# STM32F103C8T6.net
KiCad netlist of a schematic drawn in Altium Designer
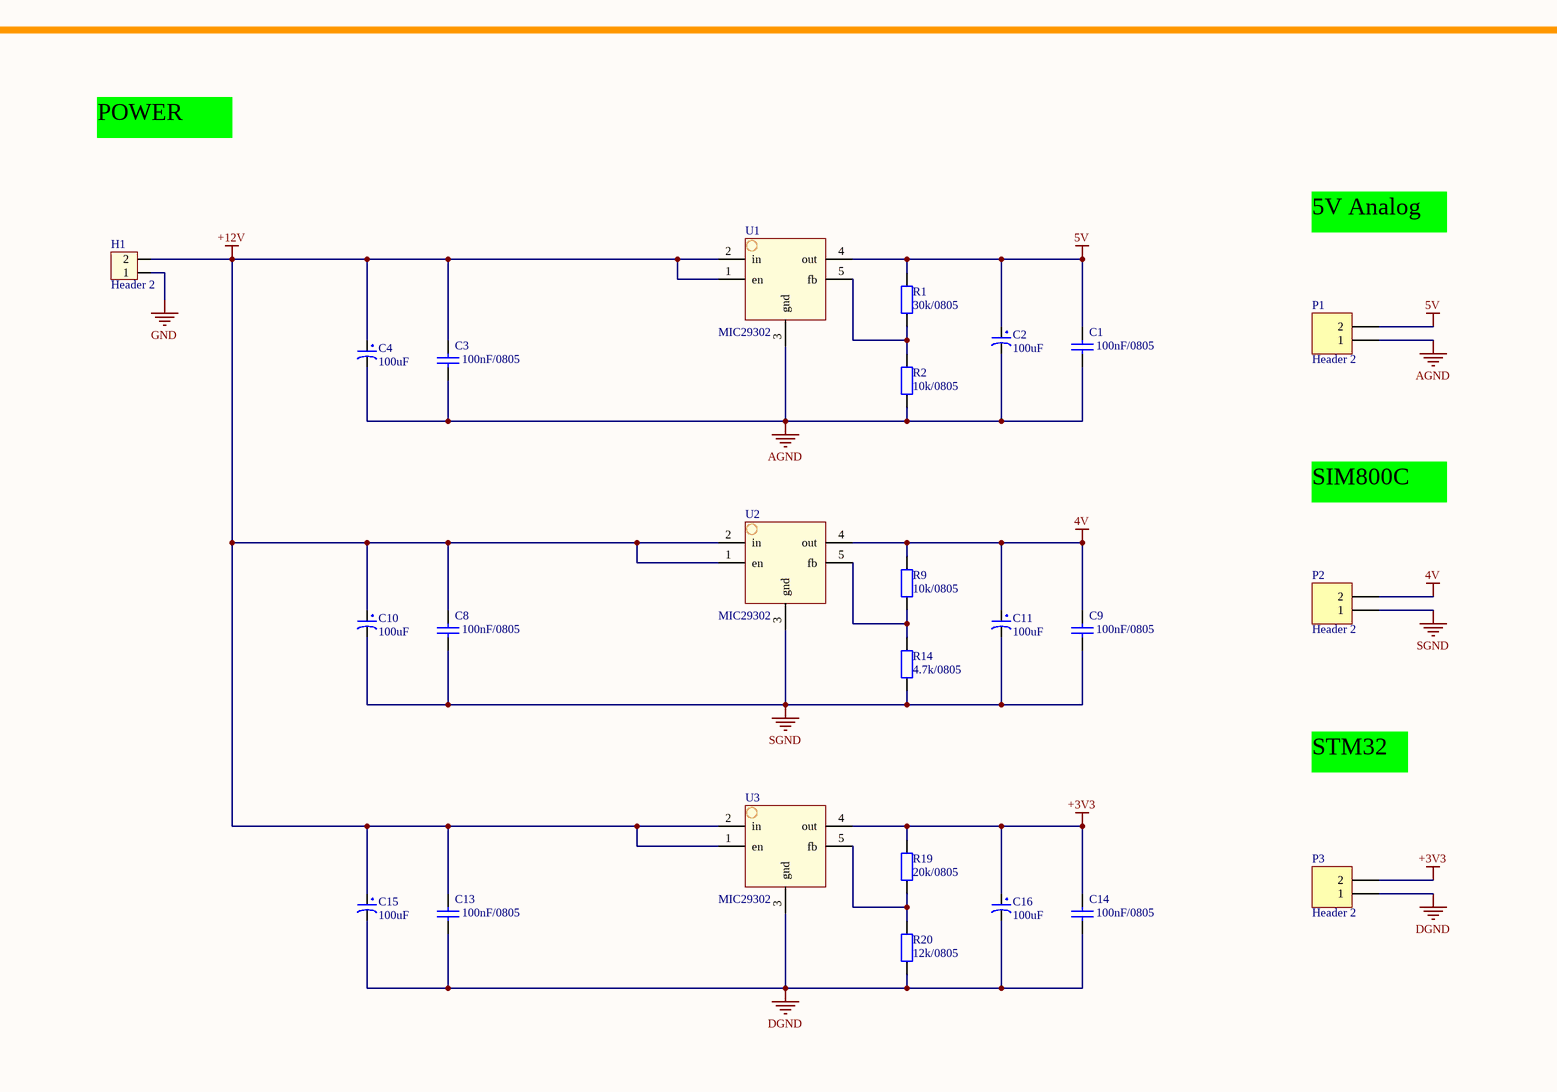
[diagram p0: STM32F103C8T6.SchDoc, top left]
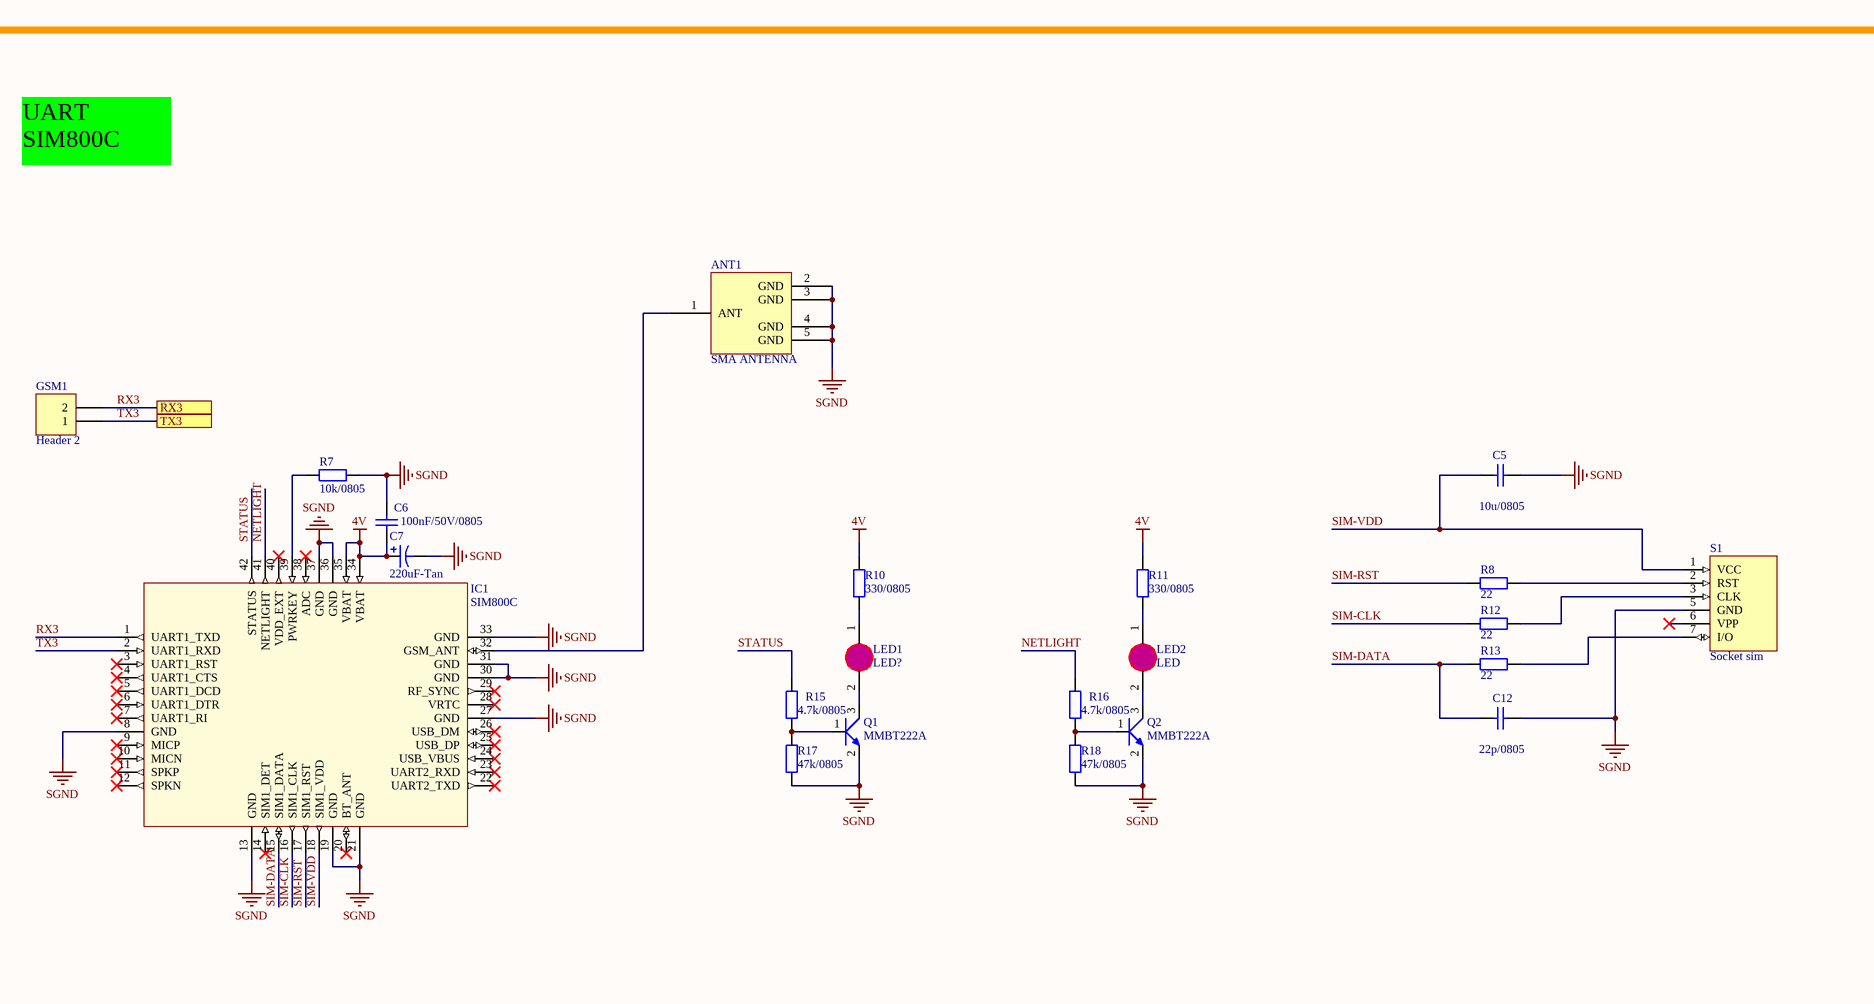
[diagram p1: STM32F103C8T6.SchDoc, top right]
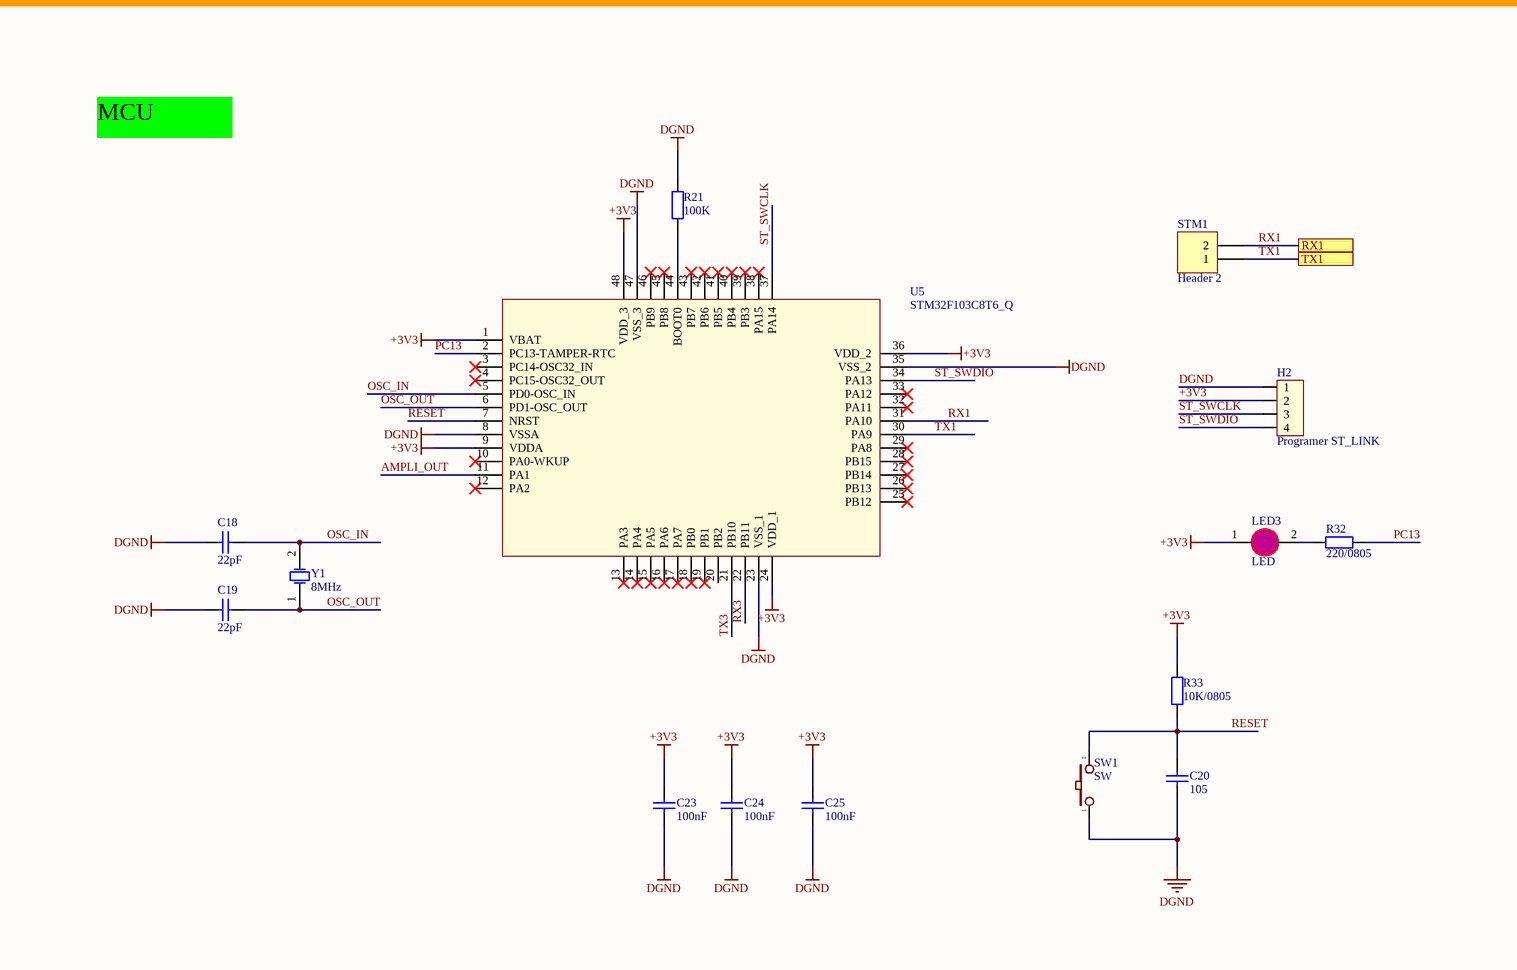
[diagram p2: STM32F103C8T6.SchDoc, bottom left]
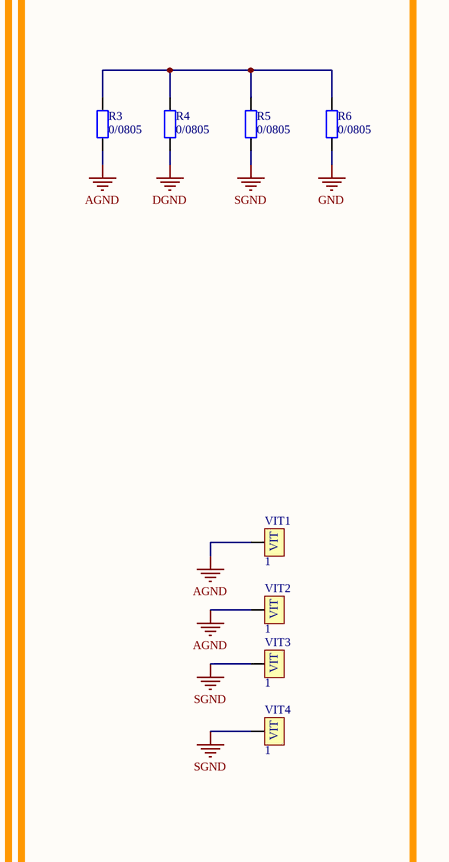
[diagram p3: STM32F103C8T6.SchDoc, bottom right]

(export (version "E")
  (design (tool "Eeschema 10.0.6"))
  (components
    (comp (ref "ANT1")
      (value "SMA ANTENNA")
      (footprint "du an mau 1:ANT-SMA-ST-F")
      (libsource (lib "Air_System_lib") (part "SMA ANTENNA"))
    )
    (comp (ref "C1")
      (value "100nF/0805")
      (footprint "C0805-2012")
      (description "100nF/50V/0805")
      (fields (field (name "PUBLISHER") "Altium Limited"))
      (libsource (lib "NBBLib 14-03-2012") (part "CapSMD"))
    )
    (comp (ref "C2")
      (value "100uF")
      (footprint "CAP_TANTA_10UF_35V")
      (description "Cap 100uF/35V - 470uF/16V")
      (libsource (lib "lpson") (part "CP3"))
    )
    (comp (ref "C3")
      (value "100nF/0805")
      (footprint "C0805-2012")
      (description "100nF/50V/0805")
      (fields (field (name "PUBLISHER") "Altium Limited"))
      (libsource (lib "NBBLib 14-03-2012") (part "CapSMD"))
    )
    (comp (ref "C4")
      (value "100uF")
      (footprint "CAP_TANTA_10UF_35V")
      (description "Cap 100uF/35V - 470uF/16V")
      (libsource (lib "lpson") (part "CP3"))
    )
    (comp (ref "C5")
      (value "10u/0805")
      (footprint "C0805-2012")
      (description "Capacitor")
      (fields (field (name "PUBLISHER") "Altium Limited"))
      (libsource (lib "NBBLib 14-03-2012") (part "CapSMD"))
    )
    (comp (ref "C6")
      (value "100nF/50V/0805")
      (footprint "C0805-2012")
      (fields (field (name "PUBLISHER") "Altium Limited"))
      (libsource (lib "NBBLib 14-03-2012") (part "CapSMD"))
    )
    (comp (ref "C7")
      (value "220uF-Tan")
      (footprint "CAP_TANTA_10UF_35V")
      (libsource (lib "Air_System_lib") (part "CAP1210-Tan"))
    )
    (comp (ref "C8")
      (value "100nF/0805")
      (footprint "C0805-2012")
      (description "100nF/50V/0805")
      (fields (field (name "PUBLISHER") "Altium Limited"))
      (libsource (lib "NBBLib 14-03-2012") (part "CapSMD"))
    )
    (comp (ref "C9")
      (value "100nF/0805")
      (footprint "C0805-2012")
      (description "100nF/50V/0805")
      (fields (field (name "PUBLISHER") "Altium Limited"))
      (libsource (lib "NBBLib 14-03-2012") (part "CapSMD"))
    )
    (comp (ref "C10")
      (value "100uF")
      (footprint "CAP_TANTA_10UF_35V")
      (description "Cap 100uF/35V - 470uF/16V")
      (libsource (lib "lpson") (part "CP3"))
    )
    (comp (ref "C11")
      (value "100uF")
      (footprint "CAP_TANTA_10UF_35V")
      (description "Cap 100uF/35V - 470uF/16V")
      (libsource (lib "lpson") (part "CP3"))
    )
    (comp (ref "C12")
      (value "22p/0805")
      (footprint "C0805-2012")
      (description "Capacitor")
      (fields (field (name "PUBLISHER") "Altium Limited"))
      (libsource (lib "NBBLib 14-03-2012") (part "CapSMD"))
    )
    (comp (ref "C13")
      (value "100nF/0805")
      (footprint "C0805-2012")
      (description "100nF/50V/0805")
      (fields (field (name "PUBLISHER") "Altium Limited"))
      (libsource (lib "NBBLib 14-03-2012") (part "CapSMD"))
    )
    (comp (ref "C14")
      (value "100nF/0805")
      (footprint "C0805-2012")
      (description "100nF/50V/0805")
      (fields (field (name "PUBLISHER") "Altium Limited"))
      (libsource (lib "NBBLib 14-03-2012") (part "CapSMD"))
    )
    (comp (ref "C15")
      (value "100uF")
      (footprint "CAP_TANTA_10UF_35V")
      (description "Cap 100uF/35V - 470uF/16V")
      (libsource (lib "lpson") (part "CP3"))
    )
    (comp (ref "C16")
      (value "100uF")
      (footprint "CAP_TANTA_10UF_35V")
      (description "Cap 100uF/35V - 470uF/16V")
      (libsource (lib "lpson") (part "CP3"))
    )
    (comp (ref "C18")
      (value "22pF")
      (footprint "C0805-2012")
      (description "Capacitor")
      (fields (field (name "Comment") "Cap") (field (name "PUBLISHER") "Altium Limited"))
      (libsource (lib "STLINKv2DIYmơi") (part "Cap"))
    )
    (comp (ref "C19")
      (value "22pF")
      (footprint "C0805-2012")
      (description "Capacitor")
      (fields (field (name "Comment") "Cap") (field (name "PUBLISHER") "Altium Limited"))
      (libsource (lib "STLINKv2DIYmơi") (part "Cap"))
    )
    (comp (ref "C20")
      (value "105")
      (footprint "C0805-2012")
      (description "Capacitor")
      (fields (field (name "Comment") "Cap") (field (name "PUBLISHER") "Altium Limited"))
      (libsource (lib "STLINKv2DIYmơi") (part "Cap"))
    )
    (comp (ref "C23")
      (value "100nF")
      (footprint "C0805-2012")
      (description "Capacitor")
      (fields (field (name "Comment") "Cap") (field (name "PUBLISHER") "Altium Limited"))
      (libsource (lib "STLINKv2DIYmơi") (part "Cap"))
    )
    (comp (ref "C24")
      (value "100nF")
      (footprint "C0805-2012")
      (description "Capacitor")
      (fields (field (name "Comment") "Cap") (field (name "PUBLISHER") "Altium Limited"))
      (libsource (lib "STLINKv2DIYmơi") (part "Cap"))
    )
    (comp (ref "C25")
      (value "100nF")
      (footprint "C0805-2012")
      (description "Capacitor")
      (fields (field (name "Comment") "Cap") (field (name "PUBLISHER") "Altium Limited"))
      (libsource (lib "STLINKv2DIYmơi") (part "Cap"))
    )
    (comp (ref "GSM1")
      (value "Header 2")
      (footprint "Header_2")
      (description "Header, 2-Pin")
      (fields (field (name "PUBLISHER") "Altium Limited"))
      (libsource (lib "NBBLib 14-03-2012") (part "Header 2"))
    )
    (comp (ref "H1")
      (value "Header 2")
      (footprint "DOMINO2_GREEN")
      (description "Header 2 (Green)")
      (libsource (lib "lpson") (part "Hed2"))
    )
    (comp (ref "H2")
      (value "Programer ST_LINK")
      (footprint "Header_4")
      (description "Header 4 (Green)")
      (libsource (lib "lpson") (part "Hed4"))
    )
    (comp (ref "IC1")
      (value "SIM800C")
      (footprint "SIM800C")
      (description "SIM800C V1.00")
      (libsource (lib "LIEMTHANH_LIB") (part "SIM800C"))
    )
    (comp (ref "LED1")
      (value "LED?")
      (footprint "Led 0805R")
      (description "LED SMD 0805")
      (libsource (lib "NBBLib 14-03-2012") (part "LED0805"))
    )
    (comp (ref "LED2")
      (value "LED")
      (footprint "Led 0805R")
      (description "LED SMD 0805")
      (libsource (lib "NBBLib 14-03-2012") (part "LED0805"))
    )
    (comp (ref "LED3")
      (value "LED")
      (footprint "Led 0805G")
      (description "LED SMD 0805")
      (libsource (lib "NBBLib 14-03-2012") (part "LED0805"))
    )
    (comp (ref "P1")
      (value "Header 2")
      (footprint "Header_2")
      (description "Header, 2-Pin")
      (fields (field (name "PUBLISHER") "Altium Limited"))
      (libsource (lib "NBBLib 14-03-2012") (part "Header 2"))
    )
    (comp (ref "P2")
      (value "Header 2")
      (footprint "Header_2")
      (description "Header, 2-Pin")
      (fields (field (name "PUBLISHER") "Altium Limited"))
      (libsource (lib "NBBLib 14-03-2012") (part "Header 2"))
    )
    (comp (ref "P3")
      (value "Header 2")
      (footprint "Header_2")
      (description "Header, 2-Pin")
      (fields (field (name "PUBLISHER") "Altium Limited"))
      (libsource (lib "NBBLib 14-03-2012") (part "Header 2"))
    )
    (comp (ref "Q1")
      (value "MMBT222A")
      (footprint "MMBT2222A")
      (libsource (lib "Air_System_lib") (part "MMBT222A"))
    )
    (comp (ref "Q2")
      (value "MMBT222A")
      (footprint "MMBT2222A")
      (libsource (lib "Air_System_lib") (part "MMBT222A"))
    )
    (comp (ref "R1")
      (value "30k/0805")
      (footprint "RESC2012(0805)")
      (description "Resistor SMD 0805")
      (fields (field (name "PUBLISHER") "Altium Limited"))
      (libsource (lib "NBBLib 14-03-2012") (part "R0805"))
    )
    (comp (ref "R2")
      (value "10k/0805")
      (footprint "RESC2012(0805)")
      (description "Resistor SMD 0805")
      (fields (field (name "PUBLISHER") "Altium Limited"))
      (libsource (lib "NBBLib 14-03-2012") (part "R0805"))
    )
    (comp (ref "R3")
      (value "0/0805")
      (footprint "RESC2012(0805)")
      (description "Resistor SMD 0805")
      (fields (field (name "Comment") "R0805") (field (name "PUBLISHER") "Altium Limited"))
      (libsource (lib "NBBLib 14-03-2012") (part "R0805"))
    )
    (comp (ref "R4")
      (value "0/0805")
      (footprint "RESC2012(0805)")
      (description "Resistor SMD 0805")
      (fields (field (name "Comment") "R0805") (field (name "PUBLISHER") "Altium Limited"))
      (libsource (lib "NBBLib 14-03-2012") (part "R0805"))
    )
    (comp (ref "R5")
      (value "0/0805")
      (footprint "RESC2012(0805)")
      (description "Resistor SMD 0805")
      (fields (field (name "Comment") "R0805") (field (name "PUBLISHER") "Altium Limited"))
      (libsource (lib "NBBLib 14-03-2012") (part "R0805"))
    )
    (comp (ref "R6")
      (value "0/0805")
      (footprint "RESC2012(0805)")
      (description "Resistor SMD 0805")
      (fields (field (name "Comment") "R0805") (field (name "PUBLISHER") "Altium Limited"))
      (libsource (lib "NBBLib 14-03-2012") (part "R0805"))
    )
    (comp (ref "R7")
      (value "10k/0805")
      (footprint "RESC2012(0805)")
      (description "Resistor SMD 0805")
      (fields (field (name "PUBLISHER") "Altium Limited"))
      (libsource (lib "") (part "R0805_2"))
    )
    (comp (ref "R8")
      (value "22")
      (footprint "RESC2012(0805)")
      (description "Resistor SMD 0805")
      (fields (field (name "Comment") "R0805") (field (name "PUBLISHER") "Altium Limited"))
      (libsource (lib "") (part "R0805_2"))
    )
    (comp (ref "R9")
      (value "10k/0805")
      (footprint "RESC2012(0805)")
      (description "Resistor SMD 0805")
      (fields (field (name "PUBLISHER") "Altium Limited"))
      (libsource (lib "NBBLib 14-03-2012") (part "R0805"))
    )
    (comp (ref "R10")
      (value "330/0805")
      (footprint "RESC2012(0805)")
      (description "Resistor SMD 0805")
      (fields (field (name "Comment") "R0805") (field (name "PUBLISHER") "Altium Limited"))
      (libsource (lib "") (part "R0805_1"))
    )
    (comp (ref "R11")
      (value "330/0805")
      (footprint "RESC2012(0805)")
      (description "Resistor SMD 0805")
      (fields (field (name "Comment") "R0805") (field (name "PUBLISHER") "Altium Limited"))
      (libsource (lib "") (part "R0805_1"))
    )
    (comp (ref "R12")
      (value "22")
      (footprint "RESC2012(0805)")
      (description "Resistor SMD 0805")
      (fields (field (name "Comment") "R0805") (field (name "PUBLISHER") "Altium Limited"))
      (libsource (lib "") (part "R0805_2"))
    )
    (comp (ref "R13")
      (value "22")
      (footprint "RESC2012(0805)")
      (description "Resistor SMD 0805")
      (fields (field (name "Comment") "R0805") (field (name "PUBLISHER") "Altium Limited"))
      (libsource (lib "") (part "R0805_2"))
    )
    (comp (ref "R14")
      (value "4.7k/0805")
      (footprint "RESC2012(0805)")
      (description "Resistor SMD 0805")
      (fields (field (name "PUBLISHER") "Altium Limited"))
      (libsource (lib "NBBLib 14-03-2012") (part "R0805"))
    )
    (comp (ref "R15")
      (value "4.7k/0805")
      (footprint "RESC2012(0805)")
      (description "Resistor SMD 0805")
      (fields (field (name "Comment") "R0805") (field (name "PUBLISHER") "Altium Limited"))
      (libsource (lib "") (part "R0805_1"))
    )
    (comp (ref "R16")
      (value "4.7k/0805")
      (footprint "RESC2012(0805)")
      (description "Resistor SMD 0805")
      (fields (field (name "Comment") "R0805") (field (name "PUBLISHER") "Altium Limited"))
      (libsource (lib "") (part "R0805_1"))
    )
    (comp (ref "R17")
      (value "47k/0805")
      (footprint "RESC2012(0805)")
      (description "Resistor SMD 0805")
      (fields (field (name "Comment") "R0805") (field (name "PUBLISHER") "Altium Limited"))
      (libsource (lib "") (part "R0805_1"))
    )
    (comp (ref "R18")
      (value "47k/0805")
      (footprint "RESC2012(0805)")
      (description "Resistor SMD 0805")
      (fields (field (name "Comment") "R0805") (field (name "PUBLISHER") "Altium Limited"))
      (libsource (lib "") (part "R0805_1"))
    )
    (comp (ref "R19")
      (value "20k/0805")
      (footprint "RESC2012(0805)")
      (description "Resistor SMD 0805")
      (fields (field (name "PUBLISHER") "Altium Limited"))
      (libsource (lib "NBBLib 14-03-2012") (part "R0805"))
    )
    (comp (ref "R20")
      (value "12k/0805")
      (footprint "RESC2012(0805)")
      (description "Resistor SMD 0805")
      (fields (field (name "PUBLISHER") "Altium Limited"))
      (libsource (lib "NBBLib 14-03-2012") (part "R0805"))
    )
    (comp (ref "R21")
      (value "100K")
      (footprint "RESC2012(0805)")
      (description "Resistor")
      (fields (field (name "Comment") "Res2") (field (name "PUBLISHER") "Altium Limited"))
      (libsource (lib "STLINKv2DIYmơi") (part "Res2"))
    )
    (comp (ref "R32")
      (value "220/0805")
      (footprint "RESC2012(0805)")
      (description "Resistor SMD 0805")
      (fields (field (name "Comment") "R0805") (field (name "PUBLISHER") "Altium Limited"))
      (libsource (lib "") (part "R0805_2"))
    )
    (comp (ref "R33")
      (value "10K/0805")
      (footprint "RESC2012(0805)")
      (description "Resistor SMD 0805")
      (fields (field (name "Comment") "R0805") (field (name "PUBLISHER") "Altium Limited"))
      (libsource (lib "") (part "R0805_1"))
    )
    (comp (ref "S1")
      (value "Socket sim")
      (footprint "Card Sim")
      (libsource (lib "Air_System_lib") (part "Socket sim"))
    )
    (comp (ref "STM1")
      (value "Header 2")
      (footprint "Header_2")
      (description "Header, 2-Pin")
      (fields (field (name "PUBLISHER") "Altium Limited"))
      (libsource (lib "NBBLib 14-03-2012") (part "Header 2"))
    )
    (comp (ref "SW1")
      (value "SW")
      (footprint "BUTTON SMD EVQ - 2PIN")
      (description "Switch button 2 pin")
      (libsource (lib "lpson") (part "SW2"))
    )
    (comp (ref "U1")
      (value "MIC29302")
      (footprint "MIC29302")
      (description "SOC")
      (libsource (lib "PART2") (part "MIC29302"))
    )
    (comp (ref "U2")
      (value "MIC29302")
      (footprint "MIC29302")
      (description "SOC")
      (libsource (lib "PART2") (part "MIC29302"))
    )
    (comp (ref "U3")
      (value "MIC29302")
      (footprint "MIC29302")
      (description "SOC")
      (libsource (lib "PART2") (part "MIC29302"))
    )
    (comp (ref "U5")
      (value "STM32F103C8T6_Q")
      (footprint "STM32F103C8T6_Q")
      (libsource (lib "SCHSTM32F103C8T6_Q") (part "STM32F103C8T6_Q"))
    )
    (comp (ref "VIT1")
      (value "1")
      (footprint "VIT")
      (description "Oc Vit")
      (libsource (lib "lpson") (part "VIT"))
    )
    (comp (ref "VIT2")
      (value "1")
      (footprint "VIT")
      (description "Oc Vit")
      (libsource (lib "lpson") (part "VIT"))
    )
    (comp (ref "VIT3")
      (value "1")
      (footprint "VIT")
      (description "Oc Vit")
      (libsource (lib "lpson") (part "VIT"))
    )
    (comp (ref "VIT4")
      (value "1")
      (footprint "VIT")
      (description "Oc Vit")
      (libsource (lib "lpson") (part "VIT"))
    )
    (comp (ref "Y1")
      (value "8MHz")
      (footprint "CRYSTAL")
      (description "Crystal Oscillator")
      (fields (field (name "PUBLISHER") "Altium Limited"))
      (libsource (lib "STLINKv2DIYmơi") (part "XTAL"))
    )
  )
  (nets
    (net (code "1") (name "+3V3") (class "Default")
      (node (ref "C14") (pin "2") (pinfunction "2_2") (pintype "passive"))
      (node (ref "C16") (pin "1") (pinfunction "1_1") (pintype "passive"))
      (node (ref "C23") (pin "2") (pinfunction "2_2") (pintype "passive"))
      (node (ref "C24") (pin "2") (pinfunction "2_2") (pintype "passive"))
      (node (ref "C25") (pin "2") (pinfunction "2_2") (pintype "passive"))
      (node (ref "H2") (pin "2") (pinfunction "2_2") (pintype "passive"))
      (node (ref "LED3") (pin "1") (pinfunction "A_1") (pintype "passive"))
      (node (ref "P3") (pin "2") (pinfunction "2_2") (pintype "passive"))
      (node (ref "R19") (pin "2") (pinfunction "2_2") (pintype "passive"))
      (node (ref "R33") (pin "1") (pinfunction "1_1") (pintype "passive"))
      (node (ref "U3") (pin "4") (pinfunction "out_4") (pintype "passive"))
      (node (ref "U5") (pin "1") (pinfunction "VBAT_1") (pintype "passive"))
      (node (ref "U5") (pin "24") (pinfunction "VDD_1_24") (pintype "passive"))
      (node (ref "U5") (pin "36") (pinfunction "VDD_2_36") (pintype "passive"))
      (node (ref "U5") (pin "48") (pinfunction "VDD_3_48") (pintype "passive"))
      (node (ref "U5") (pin "9") (pinfunction "VDDA_9") (pintype "passive"))
    )
    (net (code "2") (name "+12V") (class "Default")
      (node (ref "C10") (pin "1") (pinfunction "1_1") (pintype "passive"))
      (node (ref "C13") (pin "2") (pinfunction "2_2") (pintype "passive"))
      (node (ref "C15") (pin "1") (pinfunction "1_1") (pintype "passive"))
      (node (ref "C3") (pin "2") (pinfunction "2_2") (pintype "passive"))
      (node (ref "C4") (pin "1") (pinfunction "1_1") (pintype "passive"))
      (node (ref "C8") (pin "2") (pinfunction "2_2") (pintype "passive"))
      (node (ref "H1") (pin "2") (pinfunction "2_2") (pintype "passive"))
      (node (ref "U1") (pin "1") (pinfunction "en_1") (pintype "passive"))
      (node (ref "U1") (pin "2") (pinfunction "in_2") (pintype "passive"))
      (node (ref "U2") (pin "1") (pinfunction "en_1") (pintype "passive"))
      (node (ref "U2") (pin "2") (pinfunction "in_2") (pintype "passive"))
      (node (ref "U3") (pin "1") (pinfunction "en_1") (pintype "passive"))
      (node (ref "U3") (pin "2") (pinfunction "in_2") (pintype "passive"))
    )
    (net (code "4") (name "/AMPLI_OUT") (class "Default")
      (node (ref "U5") (pin "11") (pinfunction "PA1_11") (pintype "passive"))
    )
    (net (code "5") (name "/NETLIGHT") (class "Default")
      (node (ref "IC1") (pin "41") (pinfunction "NETLIGHT_41") (pintype "output"))
      (node (ref "R16") (pin "1") (pinfunction "1_1") (pintype "passive"))
    )
    (net (code "6") (name "/OSC_IN") (class "Default")
      (node (ref "C18") (pin "2") (pinfunction "2_2") (pintype "passive"))
      (node (ref "U5") (pin "5") (pinfunction "PD0-OSC_IN_5") (pintype "passive"))
      (node (ref "Y1") (pin "2") (pinfunction "OSC2_2") (pintype "passive"))
    )
    (net (code "7") (name "/OSC_OUT") (class "Default")
      (node (ref "C19") (pin "2") (pinfunction "2_2") (pintype "passive"))
      (node (ref "U5") (pin "6") (pinfunction "PD1-OSC_OUT_6") (pintype "passive"))
      (node (ref "Y1") (pin "1") (pinfunction "OSC1_1") (pintype "passive"))
    )
    (net (code "8") (name "/PC13") (class "Default")
      (node (ref "R32") (pin "2") (pinfunction "2_2") (pintype "passive"))
      (node (ref "U5") (pin "2") (pinfunction "PC13-TAMPER-RTC_2") (pintype "passive"))
    )
    (net (code "9") (name "/RESET") (class "Default")
      (node (ref "C20") (pin "2") (pinfunction "2_2") (pintype "passive"))
      (node (ref "R33") (pin "2") (pinfunction "2_2") (pintype "passive"))
      (node (ref "SW1") (pin "2") (pinfunction "2_2") (pintype "passive"))
      (node (ref "U5") (pin "7") (pinfunction "NRST_7") (pintype "passive"))
    )
    (net (code "10") (name "/RX1") (class "Default")
      (node (ref "STM1") (pin "2") (pinfunction "2_2") (pintype "passive"))
      (node (ref "U5") (pin "31") (pinfunction "PA10_31") (pintype "passive"))
    )
    (net (code "11") (name "/RX3") (class "Default")
      (node (ref "GSM1") (pin "2") (pinfunction "2_2") (pintype "passive"))
      (node (ref "IC1") (pin "1") (pinfunction "UART1_TXD_1") (pintype "output"))
      (node (ref "U5") (pin "22") (pinfunction "PB11_22") (pintype "passive"))
    )
    (net (code "12") (name "/SIM-CLK") (class "Default")
      (node (ref "IC1") (pin "16") (pinfunction "SIM1_CLK_16") (pintype "output"))
      (node (ref "R12") (pin "1") (pinfunction "1_1") (pintype "passive"))
    )
    (net (code "13") (name "/SIM-DATA") (class "Default")
      (node (ref "C12") (pin "1") (pinfunction "1_1") (pintype "passive"))
      (node (ref "IC1") (pin "15") (pinfunction "SIM1_DATA_15") (pintype "bidirectional"))
      (node (ref "R13") (pin "1") (pinfunction "1_1") (pintype "passive"))
    )
    (net (code "14") (name "/SIM-RST") (class "Default")
      (node (ref "IC1") (pin "17") (pinfunction "SIM1_RST_17") (pintype "output"))
      (node (ref "R8") (pin "1") (pinfunction "1_1") (pintype "passive"))
    )
    (net (code "15") (name "/SIM-VDD") (class "Default")
      (node (ref "C5") (pin "1") (pinfunction "1_1") (pintype "passive"))
      (node (ref "IC1") (pin "18") (pinfunction "SIM1_VDD_18") (pintype "output"))
      (node (ref "S1") (pin "1") (pinfunction "VCC_1") (pintype "input"))
    )
    (net (code "16") (name "/STATUS") (class "Default")
      (node (ref "IC1") (pin "42") (pinfunction "STATUS_42") (pintype "output"))
      (node (ref "R15") (pin "1") (pinfunction "1_1") (pintype "passive"))
    )
    (net (code "17") (name "/ST_SWCLK") (class "Default")
      (node (ref "H2") (pin "3") (pinfunction "3_3") (pintype "passive"))
      (node (ref "U5") (pin "37") (pinfunction "PA14_37") (pintype "passive"))
    )
    (net (code "18") (name "/ST_SWDIO") (class "Default")
      (node (ref "H2") (pin "4") (pinfunction "4_4") (pintype "passive"))
      (node (ref "U5") (pin "34") (pinfunction "PA13_34") (pintype "passive"))
    )
    (net (code "19") (name "/TX1") (class "Default")
      (node (ref "STM1") (pin "1") (pinfunction "1_1") (pintype "passive"))
      (node (ref "U5") (pin "30") (pinfunction "PA9_30") (pintype "passive"))
    )
    (net (code "20") (name "/TX3") (class "Default")
      (node (ref "GSM1") (pin "1") (pinfunction "1_1") (pintype "passive"))
      (node (ref "IC1") (pin "2") (pinfunction "UART1_RXD_2") (pintype "input"))
      (node (ref "U5") (pin "21") (pinfunction "PB10_21") (pintype "passive"))
    )
    (net (code "21") (name "4V") (class "Default")
      (node (ref "C11") (pin "1") (pinfunction "1_1") (pintype "passive"))
      (node (ref "C6") (pin "1") (pinfunction "1_1") (pintype "passive"))
      (node (ref "C7") (pin "1") (pinfunction "1_1") (pintype "passive"))
      (node (ref "C9") (pin "2") (pinfunction "2_2") (pintype "passive"))
      (node (ref "IC1") (pin "34") (pinfunction "VBAT_34") (pintype "input"))
      (node (ref "IC1") (pin "35") (pinfunction "VBAT_35") (pintype "input"))
      (node (ref "P2") (pin "2") (pinfunction "2_2") (pintype "passive"))
      (node (ref "R10") (pin "1") (pinfunction "1_1") (pintype "passive"))
      (node (ref "R11") (pin "1") (pinfunction "1_1") (pintype "passive"))
      (node (ref "R9") (pin "2") (pinfunction "2_2") (pintype "passive"))
      (node (ref "U2") (pin "4") (pinfunction "out_4") (pintype "passive"))
    )
    (net (code "22") (name "5V") (class "Default")
      (node (ref "C1") (pin "2") (pinfunction "2_2") (pintype "passive"))
      (node (ref "C2") (pin "1") (pinfunction "1_1") (pintype "passive"))
      (node (ref "P1") (pin "2") (pinfunction "2_2") (pintype "passive"))
      (node (ref "R1") (pin "2") (pinfunction "2_2") (pintype "passive"))
      (node (ref "U1") (pin "4") (pinfunction "out_4") (pintype "passive"))
    )
    (net (code "23") (name "AGND") (class "Default")
      (node (ref "C1") (pin "1") (pinfunction "1_1") (pintype "passive"))
      (node (ref "C2") (pin "2") (pinfunction "2_2") (pintype "passive"))
      (node (ref "C3") (pin "1") (pinfunction "1_1") (pintype "passive"))
      (node (ref "C4") (pin "2") (pinfunction "2_2") (pintype "passive"))
      (node (ref "P1") (pin "1") (pinfunction "1_1") (pintype "passive"))
      (node (ref "R2") (pin "1") (pinfunction "1_1") (pintype "passive"))
      (node (ref "R3") (pin "1") (pinfunction "1_1") (pintype "passive"))
      (node (ref "U1") (pin "3") (pinfunction "gnd_3") (pintype "passive"))
      (node (ref "VIT1") (pin "VIT1") (pinfunction "1_VIT1") (pintype "passive"))
      (node (ref "VIT2") (pin "VIT1") (pinfunction "1_VIT1") (pintype "passive"))
    )
    (net (code "24") (name "DGND") (class "Default")
      (node (ref "C13") (pin "1") (pinfunction "1_1") (pintype "passive"))
      (node (ref "C14") (pin "1") (pinfunction "1_1") (pintype "passive"))
      (node (ref "C15") (pin "2") (pinfunction "2_2") (pintype "passive"))
      (node (ref "C16") (pin "2") (pinfunction "2_2") (pintype "passive"))
      (node (ref "C18") (pin "1") (pinfunction "1_1") (pintype "passive"))
      (node (ref "C19") (pin "1") (pinfunction "1_1") (pintype "passive"))
      (node (ref "C20") (pin "1") (pinfunction "1_1") (pintype "passive"))
      (node (ref "C23") (pin "1") (pinfunction "1_1") (pintype "passive"))
      (node (ref "C24") (pin "1") (pinfunction "1_1") (pintype "passive"))
      (node (ref "C25") (pin "1") (pinfunction "1_1") (pintype "passive"))
      (node (ref "H2") (pin "1") (pinfunction "1_1") (pintype "passive"))
      (node (ref "P3") (pin "1") (pinfunction "1_1") (pintype "passive"))
      (node (ref "R20") (pin "1") (pinfunction "1_1") (pintype "passive"))
      (node (ref "R21") (pin "2") (pinfunction "2_2") (pintype "passive"))
      (node (ref "R4") (pin "1") (pinfunction "1_1") (pintype "passive"))
      (node (ref "SW1") (pin "1") (pinfunction "1_1") (pintype "passive"))
      (node (ref "U3") (pin "3") (pinfunction "gnd_3") (pintype "passive"))
      (node (ref "U5") (pin "23") (pinfunction "VSS_1_23") (pintype "passive"))
      (node (ref "U5") (pin "35") (pinfunction "VSS_2_35") (pintype "passive"))
      (node (ref "U5") (pin "47") (pinfunction "VSS_3_47") (pintype "passive"))
      (node (ref "U5") (pin "8") (pinfunction "VSSA_8") (pintype "passive"))
    )
    (net (code "25") (name "GND") (class "Default")
      (node (ref "H1") (pin "1") (pinfunction "1_1") (pintype "passive"))
      (node (ref "R6") (pin "1") (pinfunction "1_1") (pintype "passive"))
    )
    (net (code "26") (name "Net-(ANT1-ANT)") (class "Default")
      (node (ref "ANT1") (pin "1") (pinfunction "ANT_1") (pintype "passive"))
      (node (ref "IC1") (pin "32") (pinfunction "GSM_ANT_32") (pintype "bidirectional"))
    )
    (net (code "27") (name "Net-(IC1-PWRKEY)") (class "Default")
      (node (ref "IC1") (pin "39") (pinfunction "PWRKEY_39") (pintype "input"))
      (node (ref "R7") (pin "1") (pinfunction "1_1") (pintype "passive"))
    )
    (net (code "28") (name "Net-(LED1-A)") (class "Default")
      (node (ref "LED1") (pin "1") (pinfunction "A_1") (pintype "passive"))
      (node (ref "R10") (pin "2") (pinfunction "2_2") (pintype "passive"))
    )
    (net (code "29") (name "Net-(LED1-K)") (class "Default")
      (node (ref "LED1") (pin "2") (pinfunction "K_2") (pintype "passive"))
      (node (ref "Q1") (pin "3") (pinfunction "3_3") (pintype "passive"))
    )
    (net (code "30") (name "Net-(LED2-A)") (class "Default")
      (node (ref "LED2") (pin "1") (pinfunction "A_1") (pintype "passive"))
      (node (ref "R11") (pin "2") (pinfunction "2_2") (pintype "passive"))
    )
    (net (code "31") (name "Net-(LED2-K)") (class "Default")
      (node (ref "LED2") (pin "2") (pinfunction "K_2") (pintype "passive"))
      (node (ref "Q2") (pin "3") (pinfunction "3_3") (pintype "passive"))
    )
    (net (code "32") (name "Net-(LED3-K)") (class "Default")
      (node (ref "LED3") (pin "2") (pinfunction "K_2") (pintype "passive"))
      (node (ref "R32") (pin "1") (pinfunction "1_1") (pintype "passive"))
    )
    (net (code "33") (name "Net-(Q1-Pad1)") (class "Default")
      (node (ref "Q1") (pin "1") (pinfunction "1_1") (pintype "passive"))
      (node (ref "R15") (pin "2") (pinfunction "2_2") (pintype "passive"))
      (node (ref "R17") (pin "1") (pinfunction "1_1") (pintype "passive"))
    )
    (net (code "34") (name "Net-(Q2-Pad1)") (class "Default")
      (node (ref "Q2") (pin "1") (pinfunction "1_1") (pintype "passive"))
      (node (ref "R16") (pin "2") (pinfunction "2_2") (pintype "passive"))
      (node (ref "R18") (pin "1") (pinfunction "1_1") (pintype "passive"))
    )
    (net (code "35") (name "Net-(R3-Pad2)") (class "Default")
      (node (ref "R3") (pin "2") (pinfunction "2_2") (pintype "passive"))
      (node (ref "R4") (pin "2") (pinfunction "2_2") (pintype "passive"))
      (node (ref "R5") (pin "2") (pinfunction "2_2") (pintype "passive"))
      (node (ref "R6") (pin "2") (pinfunction "2_2") (pintype "passive"))
    )
    (net (code "36") (name "Net-(S1-CLK)") (class "Default")
      (node (ref "R12") (pin "2") (pinfunction "2_2") (pintype "passive"))
      (node (ref "S1") (pin "3") (pinfunction "CLK_3") (pintype "input"))
    )
    (net (code "37") (name "Net-(S1-I{slash}O)") (class "Default")
      (node (ref "R13") (pin "2") (pinfunction "2_2") (pintype "passive"))
      (node (ref "S1") (pin "7") (pinfunction "I/O_7") (pintype "bidirectional"))
    )
    (net (code "38") (name "Net-(S1-RST)") (class "Default")
      (node (ref "R8") (pin "2") (pinfunction "2_2") (pintype "passive"))
      (node (ref "S1") (pin "2") (pinfunction "RST_2") (pintype "input"))
    )
    (net (code "39") (name "Net-(U1-fb)") (class "Default")
      (node (ref "R1") (pin "1") (pinfunction "1_1") (pintype "passive"))
      (node (ref "R2") (pin "2") (pinfunction "2_2") (pintype "passive"))
      (node (ref "U1") (pin "5") (pinfunction "fb_5") (pintype "passive"))
    )
    (net (code "40") (name "Net-(U2-fb)") (class "Default")
      (node (ref "R14") (pin "2") (pinfunction "2_2") (pintype "passive"))
      (node (ref "R9") (pin "1") (pinfunction "1_1") (pintype "passive"))
      (node (ref "U2") (pin "5") (pinfunction "fb_5") (pintype "passive"))
    )
    (net (code "41") (name "Net-(U3-fb)") (class "Default")
      (node (ref "R19") (pin "1") (pinfunction "1_1") (pintype "passive"))
      (node (ref "R20") (pin "2") (pinfunction "2_2") (pintype "passive"))
      (node (ref "U3") (pin "5") (pinfunction "fb_5") (pintype "passive"))
    )
    (net (code "42") (name "Net-(U5-BOOT0)") (class "Default")
      (node (ref "R21") (pin "1") (pinfunction "1_1") (pintype "passive"))
      (node (ref "U5") (pin "44") (pinfunction "BOOT0_44") (pintype "passive"))
    )
    (net (code "43") (name "SGND") (class "Default")
      (node (ref "ANT1") (pin "2") (pinfunction "GND_2") (pintype "passive"))
      (node (ref "ANT1") (pin "3") (pinfunction "GND_3") (pintype "passive"))
      (node (ref "ANT1") (pin "4") (pinfunction "GND_4") (pintype "passive"))
      (node (ref "ANT1") (pin "5") (pinfunction "GND_5") (pintype "passive"))
      (node (ref "C10") (pin "2") (pinfunction "2_2") (pintype "passive"))
      (node (ref "C11") (pin "2") (pinfunction "2_2") (pintype "passive"))
      (node (ref "C12") (pin "2") (pinfunction "2_2") (pintype "passive"))
      (node (ref "C5") (pin "2") (pinfunction "2_2") (pintype "passive"))
      (node (ref "C6") (pin "2") (pinfunction "2_2") (pintype "passive"))
      (node (ref "C7") (pin "2") (pinfunction "2_2") (pintype "passive"))
      (node (ref "C8") (pin "1") (pinfunction "1_1") (pintype "passive"))
      (node (ref "C9") (pin "1") (pinfunction "1_1") (pintype "passive"))
      (node (ref "IC1") (pin "13") (pinfunction "GND_13") (pintype "power_in"))
      (node (ref "IC1") (pin "19") (pinfunction "GND_19") (pintype "power_in"))
      (node (ref "IC1") (pin "21") (pinfunction "GND_21") (pintype "power_in"))
      (node (ref "IC1") (pin "27") (pinfunction "GND_27") (pintype "power_in"))
      (node (ref "IC1") (pin "30") (pinfunction "GND_30") (pintype "power_in"))
      (node (ref "IC1") (pin "31") (pinfunction "GND_31") (pintype "power_in"))
      (node (ref "IC1") (pin "33") (pinfunction "GND_33") (pintype "power_in"))
      (node (ref "IC1") (pin "36") (pinfunction "GND_36") (pintype "power_in"))
      (node (ref "IC1") (pin "37") (pinfunction "GND_37") (pintype "power_in"))
      (node (ref "IC1") (pin "8") (pinfunction "GND_8") (pintype "power_in"))
      (node (ref "P2") (pin "1") (pinfunction "1_1") (pintype "passive"))
      (node (ref "Q1") (pin "2") (pinfunction "2_2") (pintype "passive"))
      (node (ref "Q2") (pin "2") (pinfunction "2_2") (pintype "passive"))
      (node (ref "R14") (pin "1") (pinfunction "1_1") (pintype "passive"))
      (node (ref "R17") (pin "2") (pinfunction "2_2") (pintype "passive"))
      (node (ref "R18") (pin "2") (pinfunction "2_2") (pintype "passive"))
      (node (ref "R5") (pin "1") (pinfunction "1_1") (pintype "passive"))
      (node (ref "R7") (pin "2") (pinfunction "2_2") (pintype "passive"))
      (node (ref "S1") (pin "5") (pinfunction "GND_5") (pintype "passive"))
      (node (ref "U2") (pin "3") (pinfunction "gnd_3") (pintype "passive"))
      (node (ref "VIT3") (pin "VIT1") (pinfunction "1_VIT1") (pintype "passive"))
      (node (ref "VIT4") (pin "VIT1") (pinfunction "1_VIT1") (pintype "passive"))
    )
    (net (code "44") (name "unconnected-(IC1-ADC-Pad38)") (class "Default")
      (node (ref "IC1") (pin "38") (pinfunction "ADC_38") (pintype "input+no_connect"))
    )
    (net (code "45") (name "unconnected-(IC1-BT_ANT-Pad20)") (class "Default")
      (node (ref "IC1") (pin "20") (pinfunction "BT_ANT_20") (pintype "bidirectional+no_connect"))
    )
    (net (code "46") (name "unconnected-(IC1-MICN-Pad10)") (class "Default")
      (node (ref "IC1") (pin "10") (pinfunction "MICN_10") (pintype "input+no_connect"))
    )
    (net (code "47") (name "unconnected-(IC1-MICP-Pad9)") (class "Default")
      (node (ref "IC1") (pin "9") (pinfunction "MICP_9") (pintype "input+no_connect"))
    )
    (net (code "48") (name "unconnected-(IC1-RF_SYNC-Pad29)") (class "Default")
      (node (ref "IC1") (pin "29") (pinfunction "RF_SYNC_29") (pintype "output+no_connect"))
    )
    (net (code "49") (name "unconnected-(IC1-SIM1_DET-Pad14)") (class "Default")
      (node (ref "IC1") (pin "14") (pinfunction "SIM1_DET_14") (pintype "input+no_connect"))
    )
    (net (code "50") (name "unconnected-(IC1-SPKN-Pad12)") (class "Default")
      (node (ref "IC1") (pin "12") (pinfunction "SPKN_12") (pintype "output+no_connect"))
    )
    (net (code "51") (name "unconnected-(IC1-SPKP-Pad11)") (class "Default")
      (node (ref "IC1") (pin "11") (pinfunction "SPKP_11") (pintype "output+no_connect"))
    )
    (net (code "52") (name "unconnected-(IC1-UART1_CTS-Pad4)") (class "Default")
      (node (ref "IC1") (pin "4") (pinfunction "UART1_CTS_4") (pintype "output+no_connect"))
    )
    (net (code "53") (name "unconnected-(IC1-UART1_DCD-Pad5)") (class "Default")
      (node (ref "IC1") (pin "5") (pinfunction "UART1_DCD_5") (pintype "output+no_connect"))
    )
    (net (code "54") (name "unconnected-(IC1-UART1_DTR-Pad6)") (class "Default")
      (node (ref "IC1") (pin "6") (pinfunction "UART1_DTR_6") (pintype "input+no_connect"))
    )
    (net (code "55") (name "unconnected-(IC1-UART1_RI-Pad7)") (class "Default")
      (node (ref "IC1") (pin "7") (pinfunction "UART1_RI_7") (pintype "output+no_connect"))
    )
    (net (code "56") (name "unconnected-(IC1-UART1_RST-Pad3)") (class "Default")
      (node (ref "IC1") (pin "3") (pinfunction "UART1_RST_3") (pintype "input+no_connect"))
    )
    (net (code "57") (name "unconnected-(IC1-UART2_RXD-Pad23)") (class "Default")
      (node (ref "IC1") (pin "23") (pinfunction "UART2_RXD_23") (pintype "input+no_connect"))
    )
    (net (code "58") (name "unconnected-(IC1-UART2_TXD-Pad22)") (class "Default")
      (node (ref "IC1") (pin "22") (pinfunction "UART2_TXD_22") (pintype "output+no_connect"))
    )
    (net (code "59") (name "unconnected-(IC1-USB_DM-Pad26)") (class "Default")
      (node (ref "IC1") (pin "26") (pinfunction "USB_DM_26") (pintype "bidirectional+no_connect"))
    )
    (net (code "60") (name "unconnected-(IC1-USB_DP-Pad25)") (class "Default")
      (node (ref "IC1") (pin "25") (pinfunction "USB_DP_25") (pintype "bidirectional+no_connect"))
    )
    (net (code "61") (name "unconnected-(IC1-USB_VBUS-Pad24)") (class "Default")
      (node (ref "IC1") (pin "24") (pinfunction "USB_VBUS_24") (pintype "input+no_connect"))
    )
    (net (code "62") (name "unconnected-(IC1-VDD_EXT-Pad40)") (class "Default")
      (node (ref "IC1") (pin "40") (pinfunction "VDD_EXT_40") (pintype "output+no_connect"))
    )
    (net (code "63") (name "unconnected-(IC1-VRTC-Pad28)") (class "Default")
      (node (ref "IC1") (pin "28") (pinfunction "VRTC_28") (pintype "passive+no_connect"))
    )
    (net (code "64") (name "unconnected-(S1-VPP-Pad6)") (class "Default")
      (node (ref "S1") (pin "6") (pinfunction "VPP_6") (pintype "passive+no_connect"))
    )
    (net (code "65") (name "unconnected-(U5-PA0-WKUP-Pad10)") (class "Default")
      (node (ref "U5") (pin "10") (pinfunction "PA0-WKUP_10") (pintype "passive+no_connect"))
    )
    (net (code "66") (name "unconnected-(U5-PA2-Pad12)") (class "Default")
      (node (ref "U5") (pin "12") (pinfunction "PA2_12") (pintype "passive+no_connect"))
    )
    (net (code "67") (name "unconnected-(U5-PA3-Pad13)") (class "Default")
      (node (ref "U5") (pin "13") (pinfunction "PA3_13") (pintype "passive+no_connect"))
    )
    (net (code "68") (name "unconnected-(U5-PA4-Pad14)") (class "Default")
      (node (ref "U5") (pin "14") (pinfunction "PA4_14") (pintype "passive+no_connect"))
    )
    (net (code "69") (name "unconnected-(U5-PA5-Pad15)") (class "Default")
      (node (ref "U5") (pin "15") (pinfunction "PA5_15") (pintype "passive+no_connect"))
    )
    (net (code "70") (name "unconnected-(U5-PA6-Pad16)") (class "Default")
      (node (ref "U5") (pin "16") (pinfunction "PA6_16") (pintype "passive+no_connect"))
    )
    (net (code "71") (name "unconnected-(U5-PA7-Pad17)") (class "Default")
      (node (ref "U5") (pin "17") (pinfunction "PA7_17") (pintype "passive+no_connect"))
    )
    (net (code "72") (name "unconnected-(U5-PA8-Pad29)") (class "Default")
      (node (ref "U5") (pin "29") (pinfunction "PA8_29") (pintype "passive+no_connect"))
    )
    (net (code "73") (name "unconnected-(U5-PA11-Pad32)") (class "Default")
      (node (ref "U5") (pin "32") (pinfunction "PA11_32") (pintype "passive+no_connect"))
    )
    (net (code "74") (name "unconnected-(U5-PA12-Pad33)") (class "Default")
      (node (ref "U5") (pin "33") (pinfunction "PA12_33") (pintype "passive+no_connect"))
    )
    (net (code "75") (name "unconnected-(U5-PA15-Pad38)") (class "Default")
      (node (ref "U5") (pin "38") (pinfunction "PA15_38") (pintype "passive+no_connect"))
    )
    (net (code "76") (name "unconnected-(U5-PB0-Pad18)") (class "Default")
      (node (ref "U5") (pin "18") (pinfunction "PB0_18") (pintype "passive+no_connect"))
    )
    (net (code "77") (name "unconnected-(U5-PB1-Pad19)") (class "Default")
      (node (ref "U5") (pin "19") (pinfunction "PB1_19") (pintype "passive+no_connect"))
    )
    (net (code "78") (name "unconnected-(U5-PB2-Pad20)") (class "Default")
      (node (ref "U5") (pin "20") (pinfunction "PB2_20") (pintype "passive"))
    )
    (net (code "79") (name "unconnected-(U5-PB3-Pad39)") (class "Default")
      (node (ref "U5") (pin "39") (pinfunction "PB3_39") (pintype "passive+no_connect"))
    )
    (net (code "80") (name "unconnected-(U5-PB4-Pad40)") (class "Default")
      (node (ref "U5") (pin "40") (pinfunction "PB4_40") (pintype "passive+no_connect"))
    )
    (net (code "81") (name "unconnected-(U5-PB5-Pad41)") (class "Default")
      (node (ref "U5") (pin "41") (pinfunction "PB5_41") (pintype "passive+no_connect"))
    )
    (net (code "82") (name "unconnected-(U5-PB6-Pad42)") (class "Default")
      (node (ref "U5") (pin "42") (pinfunction "PB6_42") (pintype "passive+no_connect"))
    )
    (net (code "83") (name "unconnected-(U5-PB7-Pad43)") (class "Default")
      (node (ref "U5") (pin "43") (pinfunction "PB7_43") (pintype "passive+no_connect"))
    )
    (net (code "84") (name "unconnected-(U5-PB8-Pad45)") (class "Default")
      (node (ref "U5") (pin "45") (pinfunction "PB8_45") (pintype "passive+no_connect"))
    )
    (net (code "85") (name "unconnected-(U5-PB9-Pad46)") (class "Default")
      (node (ref "U5") (pin "46") (pinfunction "PB9_46") (pintype "passive+no_connect"))
    )
    (net (code "86") (name "unconnected-(U5-PB12-Pad25)") (class "Default")
      (node (ref "U5") (pin "25") (pinfunction "PB12_25") (pintype "passive+no_connect"))
    )
    (net (code "87") (name "unconnected-(U5-PB13-Pad26)") (class "Default")
      (node (ref "U5") (pin "26") (pinfunction "PB13_26") (pintype "passive+no_connect"))
    )
    (net (code "88") (name "unconnected-(U5-PB14-Pad27)") (class "Default")
      (node (ref "U5") (pin "27") (pinfunction "PB14_27") (pintype "passive+no_connect"))
    )
    (net (code "89") (name "unconnected-(U5-PB15-Pad28)") (class "Default")
      (node (ref "U5") (pin "28") (pinfunction "PB15_28") (pintype "passive+no_connect"))
    )
    (net (code "90") (name "unconnected-(U5-PC14-OSC32_IN-Pad3)") (class "Default")
      (node (ref "U5") (pin "3") (pinfunction "PC14-OSC32_IN_3") (pintype "passive+no_connect"))
    )
    (net (code "91") (name "unconnected-(U5-PC15-OSC32_OUT-Pad4)") (class "Default")
      (node (ref "U5") (pin "4") (pinfunction "PC15-OSC32_OUT_4") (pintype "passive+no_connect"))
    )
  )
)
